# POWER.net
KiCad netlist of a schematic drawn in Altium Designer
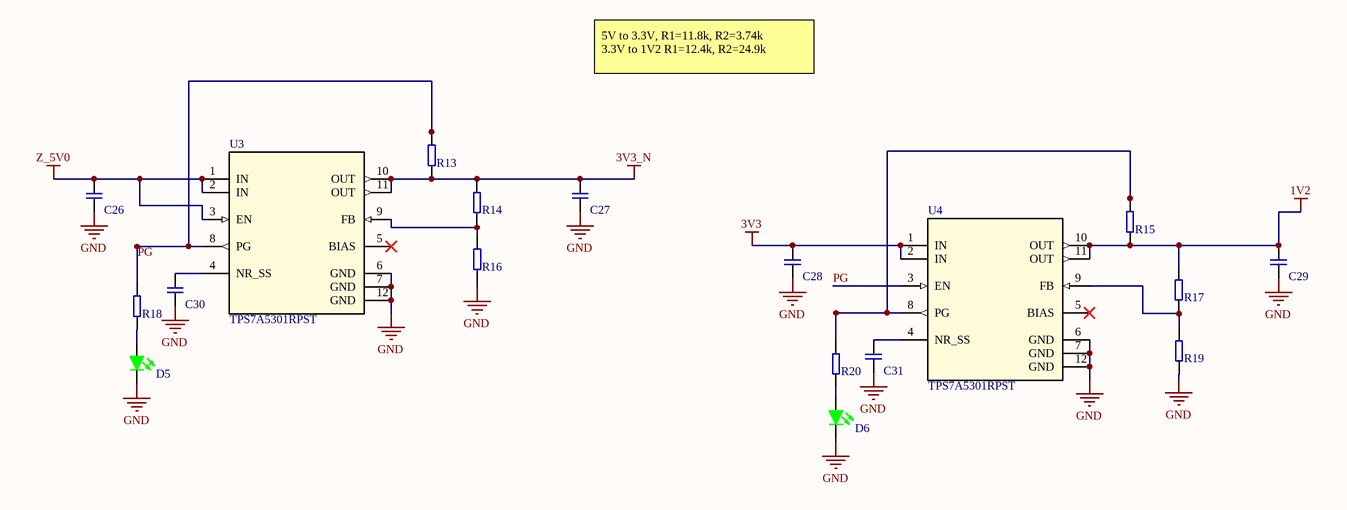
[diagram p0: POWER.SchDoc]

(export (version "E")
  (design (tool "Eeschema 10.0.6"))
  (components
    (comp (ref "C26")
      (value "47uF")
      (footprint "C1210")
      (description "MLCC (3225) 1210 47uF 16VDC ±10% X5R")
      (fields (field (name "PART NUMBER") "CL32A476KOJNNNE"))
      (libsource (lib "anayurt") (part "CAP"))
    )
    (comp (ref "C27")
      (value "47uF")
      (footprint "C0805")
      (description "MLCC (2012) 0805 47uF 10VDC ±20% X5R")
      (fields (field (name "PART NUMBER") "C2012X5R1A476M125AC"))
      (libsource (lib "anayurt") (part "CAP"))
    )
    (comp (ref "C28")
      (value "47uF")
      (footprint "C1210")
      (description "MLCC (3225) 1210 47uF 16VDC ±10% X5R")
      (fields (field (name "PART NUMBER") "CL32A476KOJNNNE"))
      (libsource (lib "anayurt") (part "CAP"))
    )
    (comp (ref "C29")
      (value "47uF")
      (footprint "C0805")
      (description "MLCC (2012) 0805 47uF 10VDC ±20% X5R")
      (fields (field (name "PART NUMBER") "C2012X5R1A476M125AC"))
      (libsource (lib "anayurt") (part "CAP"))
    )
    (comp (ref "C30")
      (value "100nF")
      (footprint "C0402")
      (description "402")
      (fields (field (name "PART NUMBER") "CL05B104KB5NNNC"))
      (libsource (lib "anayurt") (part "CAP"))
    )
    (comp (ref "C31")
      (value "100nF")
      (footprint "C0402")
      (description "402")
      (fields (field (name "PART NUMBER") "CL05B104KB5NNNC"))
      (libsource (lib "anayurt") (part "CAP"))
    )
    (comp (ref "D5")
      (value "SML-LX0603GW-TR")
      (footprint "L0603")
      (description "LED GREEN DIFFUSED SMD")
      (fields (field (name "MANUFACTURER") "Lumex Opto/Components Inc."))
      (libsource (lib "anayurt") (part "LED_GREEN"))
    )
    (comp (ref "D6")
      (value "SML-LX0603GW-TR")
      (footprint "L0603")
      (description "LED GREEN DIFFUSED SMD")
      (fields (field (name "MANUFACTURER") "Lumex Opto/Components Inc."))
      (libsource (lib "anayurt") (part "LED_GREEN"))
    )
    (comp (ref "R13")
      (value "1K")
      (footprint "R0402")
      (description "RES SMD 1K OHM 0.1% 1/16W 0402")
      (fields (field (name "PART NUMBER") "RT0402BRE071KL") (field (name "TOLERANCE") "0.1%"))
      (libsource (lib "anayurt") (part "RES"))
    )
    (comp (ref "R14")
      (value "11.8K")
      (footprint "R0603")
      (description "RES 11.8K OHM 1% 1/10W 0603")
      (fields (field (name "PART NUMBER") "RMCF0603FT11K8") (field (name "TOLERANCE") "0.1%"))
      (libsource (lib "anayurt") (part "RES"))
    )
    (comp (ref "R15")
      (value "1K")
      (footprint "R0402")
      (description "RES SMD 1K OHM 0.1% 1/16W 0402")
      (fields (field (name "PART NUMBER") "RT0402BRE071KL") (field (name "TOLERANCE") "0.1%"))
      (libsource (lib "anayurt") (part "RES"))
    )
    (comp (ref "R16")
      (value "3.74K")
      (footprint "R0603")
      (description "RES 3.74K OHM 1% 1/10W 0603")
      (fields (field (name "PART NUMBER") "RC0603FR-073K74L") (field (name "TOLERANCE") "1%"))
      (libsource (lib "anayurt") (part "RES"))
    )
    (comp (ref "R17")
      (value "12.4K")
      (footprint "R0402")
      (description "RES 12.4K OHM 1% 1/16W 0402")
      (fields (field (name "PART NUMBER") "RC0402FR-0712K4L"))
      (libsource (lib "anayurt") (part "RES"))
    )
    (comp (ref "R18")
      (value "1K")
      (footprint "R0402")
      (description "RES SMD 1K OHM 0.1% 1/16W 0402")
      (fields (field (name "PART NUMBER") "RT0402BRE071KL") (field (name "TOLERANCE") "0.1%"))
      (libsource (lib "anayurt") (part "RES"))
    )
    (comp (ref "R19")
      (value "24.9K")
      (footprint "R0402")
      (description "RES 24.9K OHM 1% 1/16W 0402")
      (fields (field (name "PART NUMBER") "RC0402FR-0724K9L"))
      (libsource (lib "anayurt") (part "RES"))
    )
    (comp (ref "R20")
      (value "1K")
      (footprint "R0402")
      (description "RES SMD 1K OHM 0.1% 1/16W 0402")
      (fields (field (name "PART NUMBER") "RT0402BRE071KL") (field (name "TOLERANCE") "0.1%"))
      (libsource (lib "anayurt") (part "RES"))
    )
    (comp (ref "U3")
      (value "TPS7A5301RPST")
      (footprint "RPS0012A-MFG")
      (fields (field (name "COPYRIGHT") "Copyright (C) 2024 Ultra Librarian. All rights reserved."))
      (libsource (lib "anayurt") (part "TPS7A5301RPST"))
    )
    (comp (ref "U4")
      (value "TPS7A5301RPST")
      (footprint "RPS0012A-MFG")
      (fields (field (name "COPYRIGHT") "Copyright (C) 2024 Ultra Librarian. All rights reserved."))
      (libsource (lib "anayurt") (part "TPS7A5301RPST"))
    )
  )
  (nets
    (net (code "1") (name "/PG") (class "Default")
      (node (ref "R13") (pin "2") (pinfunction "2_2") (pintype "passive"))
      (node (ref "R18") (pin "2") (pinfunction "2_2") (pintype "passive"))
      (node (ref "U3") (pin "8") (pinfunction "PG_8") (pintype "output"))
      (node (ref "U4") (pin "3") (pinfunction "EN_3") (pintype "input"))
    )
    (net (code "2") (name "1V2") (class "Default")
      (node (ref "C29") (pin "2") (pinfunction "2_2") (pintype "passive"))
      (node (ref "R15") (pin "1") (pinfunction "1_1") (pintype "passive"))
      (node (ref "R17") (pin "2") (pinfunction "2_2") (pintype "passive"))
      (node (ref "U4") (pin "10") (pinfunction "OUT_10") (pintype "output"))
      (node (ref "U4") (pin "11") (pinfunction "OUT_11") (pintype "output"))
    )
    (net (code "3") (name "3V3") (class "Default")
      (node (ref "C28") (pin "2") (pinfunction "2_2") (pintype "passive"))
      (node (ref "U4") (pin "1") (pinfunction "IN_1") (pintype "power_in"))
      (node (ref "U4") (pin "2") (pinfunction "IN_2") (pintype "power_in"))
    )
    (net (code "4") (name "3V3_N") (class "Default")
      (node (ref "C27") (pin "2") (pinfunction "2_2") (pintype "passive"))
      (node (ref "R13") (pin "1") (pinfunction "1_1") (pintype "passive"))
      (node (ref "R14") (pin "2") (pinfunction "2_2") (pintype "passive"))
      (node (ref "U3") (pin "10") (pinfunction "OUT_10") (pintype "output"))
      (node (ref "U3") (pin "11") (pinfunction "OUT_11") (pintype "output"))
    )
    (net (code "5") (name "GND") (class "Default")
      (node (ref "C26") (pin "1") (pinfunction "1_1") (pintype "passive"))
      (node (ref "C27") (pin "1") (pinfunction "1_1") (pintype "passive"))
      (node (ref "C28") (pin "1") (pinfunction "1_1") (pintype "passive"))
      (node (ref "C29") (pin "1") (pinfunction "1_1") (pintype "passive"))
      (node (ref "C30") (pin "1") (pinfunction "1_1") (pintype "passive"))
      (node (ref "C31") (pin "1") (pinfunction "1_1") (pintype "passive"))
      (node (ref "D5") (pin "C") (pinfunction "C_C") (pintype "passive"))
      (node (ref "D6") (pin "C") (pinfunction "C_C") (pintype "passive"))
      (node (ref "R16") (pin "1") (pinfunction "1_1") (pintype "passive"))
      (node (ref "R19") (pin "1") (pinfunction "1_1") (pintype "passive"))
      (node (ref "U3") (pin "12") (pinfunction "GND_12") (pintype "power_in"))
      (node (ref "U3") (pin "6") (pinfunction "GND_6") (pintype "power_in"))
      (node (ref "U3") (pin "7") (pinfunction "GND_7") (pintype "power_in"))
      (node (ref "U4") (pin "12") (pinfunction "GND_12") (pintype "power_in"))
      (node (ref "U4") (pin "6") (pinfunction "GND_6") (pintype "power_in"))
      (node (ref "U4") (pin "7") (pinfunction "GND_7") (pintype "power_in"))
    )
    (net (code "6") (name "Net-(D5-PadA)") (class "Default")
      (node (ref "D5") (pin "A") (pinfunction "A_A") (pintype "passive"))
      (node (ref "R18") (pin "1") (pinfunction "1_1") (pintype "passive"))
    )
    (net (code "7") (name "Net-(D6-PadA)") (class "Default")
      (node (ref "D6") (pin "A") (pinfunction "A_A") (pintype "passive"))
      (node (ref "R20") (pin "1") (pinfunction "1_1") (pintype "passive"))
    )
    (net (code "8") (name "Net-(U3-FB)") (class "Default")
      (node (ref "R14") (pin "1") (pinfunction "1_1") (pintype "passive"))
      (node (ref "R16") (pin "2") (pinfunction "2_2") (pintype "passive"))
      (node (ref "U3") (pin "9") (pinfunction "FB_9") (pintype "input"))
    )
    (net (code "9") (name "Net-(U3-NR_SS)") (class "Default")
      (node (ref "C30") (pin "2") (pinfunction "2_2") (pintype "passive"))
      (node (ref "U3") (pin "4") (pinfunction "NR_SS_4") (pintype "passive"))
    )
    (net (code "10") (name "Net-(U4-FB)") (class "Default")
      (node (ref "R17") (pin "1") (pinfunction "1_1") (pintype "passive"))
      (node (ref "R19") (pin "2") (pinfunction "2_2") (pintype "passive"))
      (node (ref "U4") (pin "9") (pinfunction "FB_9") (pintype "input"))
    )
    (net (code "11") (name "Net-(U4-NR_SS)") (class "Default")
      (node (ref "C31") (pin "2") (pinfunction "2_2") (pintype "passive"))
      (node (ref "U4") (pin "4") (pinfunction "NR_SS_4") (pintype "passive"))
    )
    (net (code "12") (name "Net-(U4-PG)") (class "Default")
      (node (ref "R15") (pin "2") (pinfunction "2_2") (pintype "passive"))
      (node (ref "R20") (pin "2") (pinfunction "2_2") (pintype "passive"))
      (node (ref "U4") (pin "8") (pinfunction "PG_8") (pintype "output"))
    )
    (net (code "13") (name "Z_5V0") (class "Default")
      (node (ref "C26") (pin "2") (pinfunction "2_2") (pintype "passive"))
      (node (ref "U3") (pin "1") (pinfunction "IN_1") (pintype "power_in"))
      (node (ref "U3") (pin "2") (pinfunction "IN_2") (pintype "power_in"))
      (node (ref "U3") (pin "3") (pinfunction "EN_3") (pintype "input"))
    )
    (net (code "14") (name "unconnected-(U3-BIAS-Pad5)") (class "Default")
      (node (ref "U3") (pin "5") (pinfunction "BIAS_5") (pintype "power_in+no_connect"))
    )
    (net (code "15") (name "unconnected-(U4-BIAS-Pad5)") (class "Default")
      (node (ref "U4") (pin "5") (pinfunction "BIAS_5") (pintype "power_in+no_connect"))
    )
  )
)
